# CKT-9000.net
KiCad netlist of a schematic drawn in EAGLE
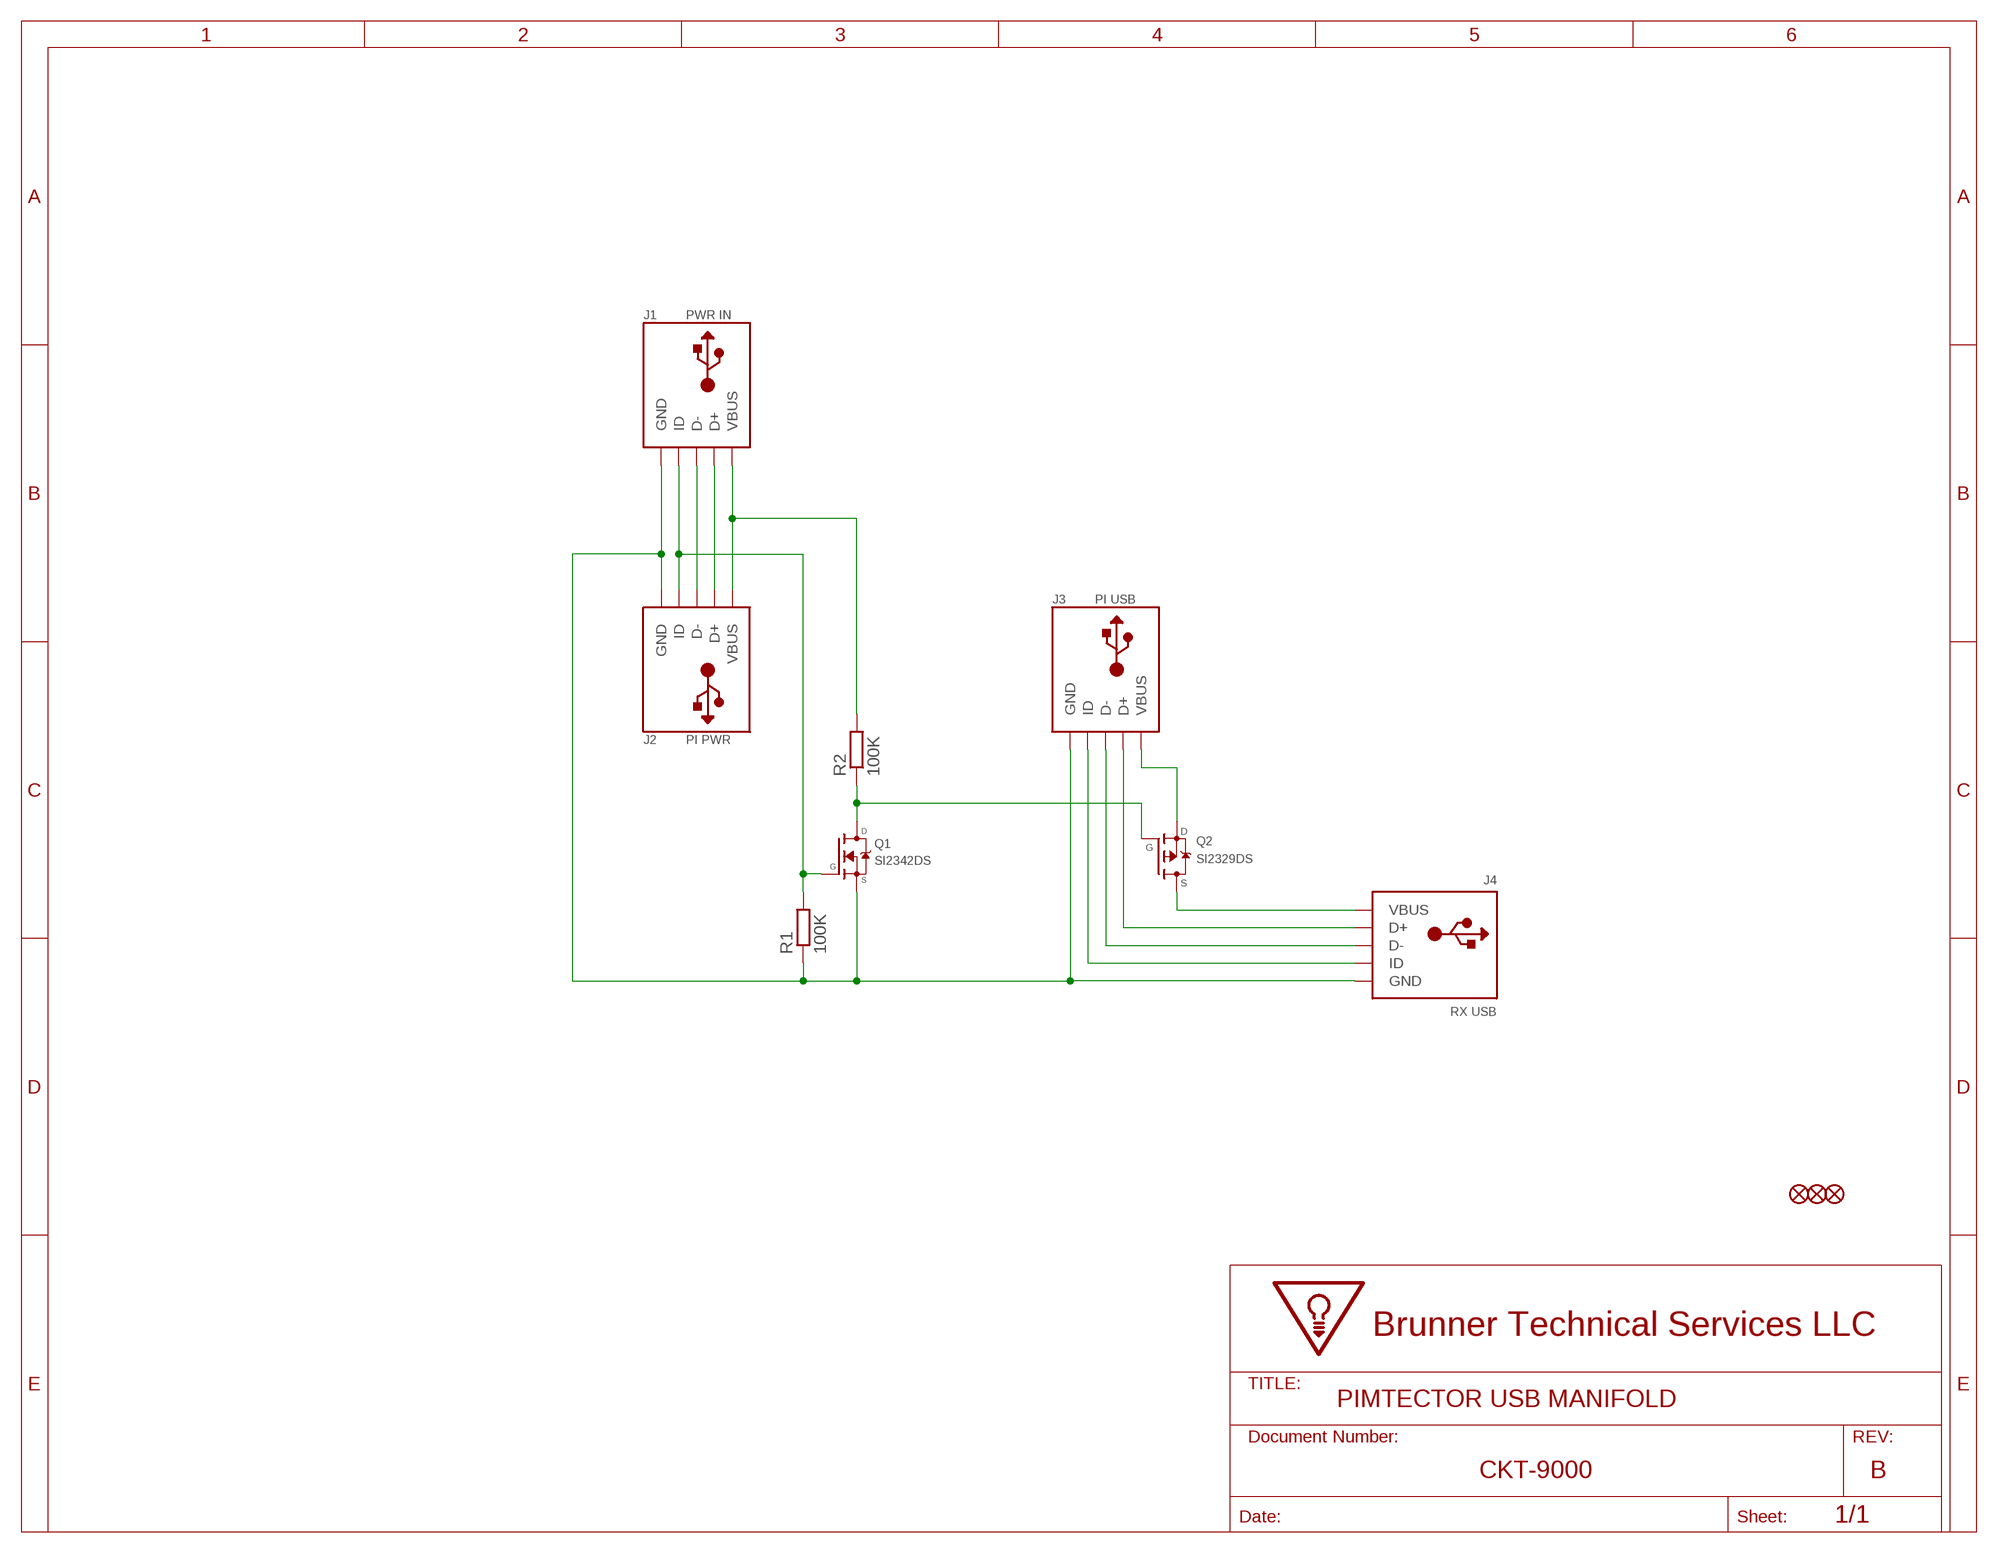
[diagram p0: schematic, sheet 1]

(export (version "E")
  (design (tool "Eeschema 10.0.6"))
  (components
    (comp (ref "FID1")
      (value "FIDUCIAL\"\"")
      (footprint "eagle-import:FIDUCIAL_1MM")
      (libsource (lib "eagle-import") (part "FIDUCIAL{dblquote}{dblquote}"))
    )
    (comp (ref "FID2")
      (value "FIDUCIAL\"\"")
      (footprint "eagle-import:FIDUCIAL_1MM")
      (libsource (lib "eagle-import") (part "FIDUCIAL{dblquote}{dblquote}"))
    )
    (comp (ref "FID3")
      (value "FIDUCIAL\"\"")
      (footprint "eagle-import:FIDUCIAL_1MM")
      (libsource (lib "eagle-import") (part "FIDUCIAL{dblquote}{dblquote}"))
    )
    (comp (ref "J1")
      (value "PWR IN")
      (footprint "eagle-import:GCT_USB3150")
      (libsource (lib "eagle-import") (part "USBMICROB"))
    )
    (comp (ref "J2")
      (value "PI PWR")
      (footprint "eagle-import:GCT_USB3150")
      (libsource (lib "eagle-import") (part "USBMICROB"))
    )
    (comp (ref "J3")
      (value "PI USB")
      (footprint "eagle-import:GCT_USB3150")
      (libsource (lib "eagle-import") (part "USBMICROB"))
    )
    (comp (ref "J4")
      (value "RX USB")
      (footprint "eagle-import:AMPHENOL_10103594")
      (libsource (lib "eagle-import") (part "USB"))
    )
    (comp (ref "Q1")
      (value "SI2342DS")
      (footprint "eagle-import:SOT23")
      (libsource (lib "eagle-import") (part "MOSFET-NREFLOW"))
    )
    (comp (ref "Q2")
      (value "SI2329DS")
      (footprint "eagle-import:SOT23")
      (libsource (lib "eagle-import") (part "MOSFET-PSOT23"))
    )
    (comp (ref "R1")
      (value "100K")
      (footprint "eagle-import:R0805")
      (libsource (lib "eagle-import") (part "R-EU_R0805"))
    )
    (comp (ref "R2")
      (value "100K")
      (footprint "eagle-import:R0805")
      (libsource (lib "eagle-import") (part "R-EU_R0805"))
    )
  )
  (nets
    (net (code "1") (name "Net-(J1-PadD+)") (class "Default")
      (node (ref "J1") (pin "D+") (pinfunction "D+_D+") (pintype "bidirectional"))
      (node (ref "J2") (pin "D+") (pinfunction "D+_D+") (pintype "bidirectional"))
    )
    (net (code "2") (name "Net-(J1-PadD-)") (class "Default")
      (node (ref "J1") (pin "D-") (pinfunction "D-_D-") (pintype "bidirectional"))
      (node (ref "J2") (pin "D-") (pinfunction "D-_D-") (pintype "bidirectional"))
    )
    (net (code "3") (name "Net-(J1-PadVBUS)") (class "Default")
      (node (ref "J1") (pin "VBUS") (pinfunction "VBUS_VBUS") (pintype "power_in"))
      (node (ref "J2") (pin "VBUS") (pinfunction "VBUS_VBUS") (pintype "power_in"))
      (node (ref "R2") (pin "2") (pinfunction "2_2") (pintype "passive"))
    )
    (net (code "4") (name "Net-(J3-PadD+)") (class "Default")
      (node (ref "J3") (pin "D+") (pinfunction "D+_D+") (pintype "bidirectional"))
      (node (ref "J4") (pin "D+") (pinfunction "D+_D+") (pintype "bidirectional"))
    )
    (net (code "5") (name "Net-(J3-PadD-)") (class "Default")
      (node (ref "J3") (pin "D-") (pinfunction "D-_D-") (pintype "bidirectional"))
      (node (ref "J4") (pin "D-") (pinfunction "D-_D-") (pintype "bidirectional"))
    )
    (net (code "6") (name "Net-(J3-PadID)") (class "Default")
      (node (ref "J3") (pin "ID") (pinfunction "ID_ID") (pintype "bidirectional"))
      (node (ref "J4") (pin "ID") (pinfunction "ID_ID") (pintype "bidirectional"))
    )
    (net (code "7") (name "Net-(Q1-D)") (class "Default")
      (node (ref "Q1") (pin "3") (pinfunction "D_3") (pintype "bidirectional"))
      (node (ref "Q2") (pin "1") (pinfunction "G_1") (pintype "passive"))
      (node (ref "R2") (pin "1") (pinfunction "1_1") (pintype "passive"))
    )
    (net (code "8") (name "Net-(Q1-G)") (class "Default")
      (node (ref "J1") (pin "ID") (pinfunction "ID_ID") (pintype "bidirectional"))
      (node (ref "J2") (pin "ID") (pinfunction "ID_ID") (pintype "bidirectional"))
      (node (ref "Q1") (pin "1") (pinfunction "G_1") (pintype "bidirectional"))
      (node (ref "R1") (pin "2") (pinfunction "2_2") (pintype "passive"))
    )
    (net (code "9") (name "Net-(Q1-S)") (class "Default")
      (node (ref "J1") (pin "GND") (pinfunction "GND_GND") (pintype "power_in"))
      (node (ref "J1") (pin "GND$1") (pinfunction "GND_GND$1") (pintype "power_in"))
      (node (ref "J1") (pin "GND$2") (pinfunction "GND_GND$2") (pintype "power_in"))
      (node (ref "J1") (pin "GND$3") (pinfunction "GND_GND$3") (pintype "power_in"))
      (node (ref "J1") (pin "GND$4") (pinfunction "GND_GND$4") (pintype "power_in"))
      (node (ref "J1") (pin "GND$5") (pinfunction "GND_GND$5") (pintype "power_in"))
      (node (ref "J1") (pin "GND$6") (pinfunction "GND_GND$6") (pintype "power_in"))
      (node (ref "J2") (pin "GND") (pinfunction "GND_GND") (pintype "power_in"))
      (node (ref "J2") (pin "GND$1") (pinfunction "GND_GND$1") (pintype "power_in"))
      (node (ref "J2") (pin "GND$2") (pinfunction "GND_GND$2") (pintype "power_in"))
      (node (ref "J2") (pin "GND$3") (pinfunction "GND_GND$3") (pintype "power_in"))
      (node (ref "J2") (pin "GND$4") (pinfunction "GND_GND$4") (pintype "power_in"))
      (node (ref "J2") (pin "GND$5") (pinfunction "GND_GND$5") (pintype "power_in"))
      (node (ref "J2") (pin "GND$6") (pinfunction "GND_GND$6") (pintype "power_in"))
      (node (ref "J3") (pin "GND") (pinfunction "GND_GND") (pintype "power_in"))
      (node (ref "J3") (pin "GND$1") (pinfunction "GND_GND$1") (pintype "power_in"))
      (node (ref "J3") (pin "GND$2") (pinfunction "GND_GND$2") (pintype "power_in"))
      (node (ref "J3") (pin "GND$3") (pinfunction "GND_GND$3") (pintype "power_in"))
      (node (ref "J3") (pin "GND$4") (pinfunction "GND_GND$4") (pintype "power_in"))
      (node (ref "J3") (pin "GND$5") (pinfunction "GND_GND$5") (pintype "power_in"))
      (node (ref "J3") (pin "GND$6") (pinfunction "GND_GND$6") (pintype "power_in"))
      (node (ref "J4") (pin "BASE@1") (pinfunction "GND_BASE@1") (pintype "power_in"))
      (node (ref "J4") (pin "BASE@2") (pinfunction "GND_BASE@2") (pintype "power_in"))
      (node (ref "J4") (pin "GND") (pinfunction "GND_GND") (pintype "power_in"))
      (node (ref "J4") (pin "SPRT@1") (pinfunction "GND_SPRT@1") (pintype "power_in"))
      (node (ref "J4") (pin "SPRT@2") (pinfunction "GND_SPRT@2") (pintype "power_in"))
      (node (ref "J4") (pin "SPRT@3") (pinfunction "GND_SPRT@3") (pintype "power_in"))
      (node (ref "J4") (pin "SPRT@4") (pinfunction "GND_SPRT@4") (pintype "power_in"))
      (node (ref "Q1") (pin "2") (pinfunction "S_2") (pintype "bidirectional"))
      (node (ref "R1") (pin "1") (pinfunction "1_1") (pintype "passive"))
    )
    (net (code "10") (name "Net-(Q2-D)") (class "Default")
      (node (ref "J4") (pin "VBUS") (pinfunction "VBUS_VBUS") (pintype "power_in"))
      (node (ref "Q2") (pin "3") (pinfunction "D_3") (pintype "passive"))
    )
    (net (code "11") (name "Net-(Q2-S)") (class "Default")
      (node (ref "J3") (pin "VBUS") (pinfunction "VBUS_VBUS") (pintype "power_in"))
      (node (ref "Q2") (pin "2") (pinfunction "S_2") (pintype "passive"))
    )
  )
)
